# CAN.net
KiCad netlist of a schematic drawn in Altium Designer
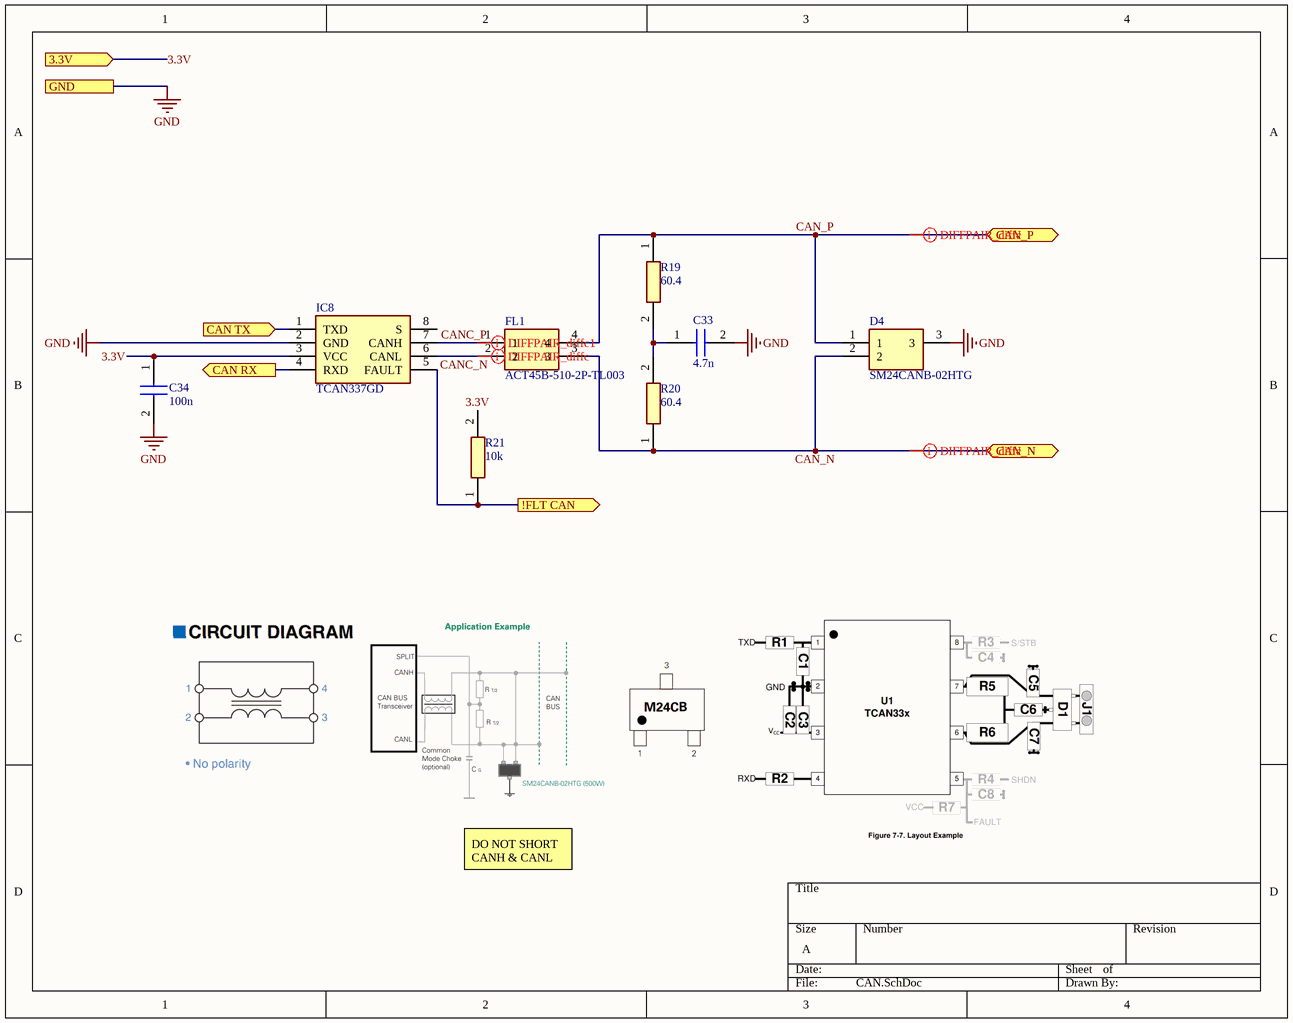
[diagram p0: CAN.SchDoc]

(export (version "E")
  (design (tool "Eeschema 10.0.6"))
  (components
    (comp (ref "C33")
      (value "4.7n")
      (footprint "SamacSys:CAPC1608X95N")
      (description "Capacitor")
      (fields (field (name "MANUFACTURER_PART_NUMBER") "0603B472M500CT"))
      (libsource (lib "*") (part "0603B472M500CT"))
    )
    (comp (ref "C34")
      (value "100n")
      (footprint "SamacSys:CAPC1608X90N")
      (description "Capacitor")
      (fields
        (field (name "MANUFACTURER_PART_NUMBER") "06035C104J4Z2A")
        (field (name "MOUSER PART NUMBER") "581-06035C104J4Z2A")
      )
      (libsource (lib "*") (part "06035C104J4Z2A"))
    )
    (comp (ref "D4")
      (value "SM24CANB-02HTG")
      (footprint "SamacSys:SM24CANB02HTG")
      (description "TVS Diode (Bi-directional)")
      (fields (field (name "MOUSER PART NUMBER") "576-SM24CANB-02HTG"))
      (libsource (lib "*") (part "SM24CANB-02HTG"))
    )
    (comp (ref "FL1")
      (value "ACT45B-510-2P-TL003")
      (footprint "SamacSys:ACT45B1012PTL003")
      (description "Filter")
      (fields (field (name "MOUSER PART NUMBER") "810-ACT45B5102PTL003"))
      (libsource (lib "*") (part "ACT45B-510-2P-TL003"))
    )
    (comp (ref "IC8")
      (value "TCAN337GD")
      (footprint "SamacSys:SOIC127P600X175-8N")
      (description "Integrated Circuit")
      (fields (field (name "MOUSER PART NUMBER") "595-TCAN337GD"))
      (libsource (lib "*") (part "TCAN337GD"))
    )
    (comp (ref "R19")
      (value "60.4")
      (footprint "SamacSys:RESC1608X50N")
      (description "Resistor")
      (fields
        (field (name "MANUFACTURER_PART_NUMBER") "CRCW060360R4FKEA")
        (field (name "MOUSER PART NUMBER") "71-CRCW0603-60.4-E3")
      )
      (libsource (lib "") (part "CRCW060360R4FKEA_1"))
    )
    (comp (ref "R20")
      (value "60.4")
      (footprint "SamacSys:RESC1608X50N")
      (description "Resistor")
      (fields
        (field (name "MANUFACTURER_PART_NUMBER") "CRCW060360R4FKEA")
        (field (name "MOUSER PART NUMBER") "71-CRCW0603-60.4-E3")
      )
      (libsource (lib "*") (part "CRCW060360R4FKEA"))
    )
    (comp (ref "R21")
      (value "10k")
      (footprint "SamacSys:RESC1608X55N")
      (description "Resistor")
      (fields
        (field (name "MANUFACTURER_PART_NUMBER") "CRGCQ0603F10K")
        (field (name "MOUSER PART NUMBER") "279-CRGCQ0603F10K")
      )
      (libsource (lib "*") (part "CRGCQ0603F10K"))
    )
  )
  (nets
    (net (code "1") (name "/!FLT CAN") (class "Default")
      (node (ref "IC8") (pin "5") (pinfunction "FAULT_5") (pintype "passive"))
      (node (ref "R21") (pin "1") (pinfunction "1_1") (pintype "passive"))
    )
    (net (code "2") (name "/3.3V") (class "Default")
      (node (ref "C34") (pin "1") (pinfunction "1_1") (pintype "passive"))
      (node (ref "IC8") (pin "3") (pinfunction "VCC_3") (pintype "passive"))
      (node (ref "R21") (pin "2") (pinfunction "2_2") (pintype "passive"))
    )
    (net (code "3") (name "/CAN RX") (class "Default")
      (node (ref "IC8") (pin "4") (pinfunction "RXD_4") (pintype "passive"))
    )
    (net (code "4") (name "/CAN TX") (class "Default")
      (node (ref "IC8") (pin "1") (pinfunction "TXD_1") (pintype "passive"))
    )
    (net (code "5") (name "/CANC_N") (class "Default")
      (node (ref "FL1") (pin "2") (pinfunction "2_2") (pintype "passive"))
      (node (ref "IC8") (pin "6") (pinfunction "CANL_6") (pintype "passive"))
    )
    (net (code "6") (name "/CANC_P") (class "Default")
      (node (ref "FL1") (pin "1") (pinfunction "1_1") (pintype "passive"))
      (node (ref "IC8") (pin "7") (pinfunction "CANH_7") (pintype "passive"))
    )
    (net (code "7") (name "/CAN_N") (class "Default")
      (node (ref "D4") (pin "2") (pinfunction "2_2") (pintype "passive"))
      (node (ref "FL1") (pin "3") (pinfunction "3_3") (pintype "passive"))
      (node (ref "R20") (pin "1") (pinfunction "1_1") (pintype "passive"))
    )
    (net (code "8") (name "/CAN_P") (class "Default")
      (node (ref "D4") (pin "1") (pinfunction "1_1") (pintype "passive"))
      (node (ref "FL1") (pin "4") (pinfunction "4_4") (pintype "passive"))
      (node (ref "R19") (pin "1") (pinfunction "1_1") (pintype "passive"))
    )
    (net (code "9") (name "GND") (class "Default")
      (node (ref "C33") (pin "2") (pinfunction "2_2") (pintype "passive"))
      (node (ref "C34") (pin "2") (pinfunction "2_2") (pintype "passive"))
      (node (ref "D4") (pin "3") (pinfunction "3_3") (pintype "passive"))
      (node (ref "IC8") (pin "2") (pinfunction "GND_2") (pintype "passive"))
    )
    (net (code "10") (name "Net-(C33-Pad1)") (class "Default")
      (node (ref "C33") (pin "1") (pinfunction "1_1") (pintype "passive"))
      (node (ref "R19") (pin "2") (pinfunction "2_2") (pintype "passive"))
      (node (ref "R20") (pin "2") (pinfunction "2_2") (pintype "passive"))
    )
    (net (code "11") (name "unconnected-(IC8-S-Pad8)") (class "Default")
      (node (ref "IC8") (pin "8") (pinfunction "S_8") (pintype "passive"))
    )
  )
)
